# RAM_TheoreticalDiagram.net
KiCad netlist of a schematic drawn in EAGLE
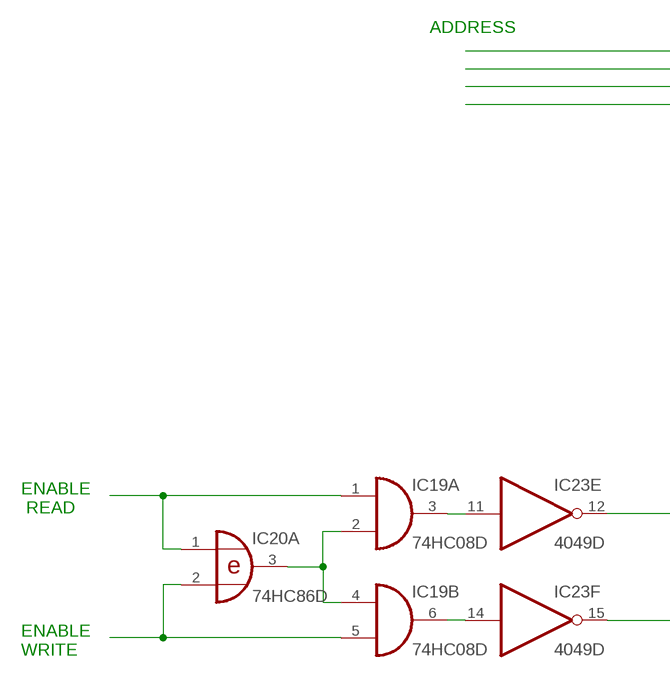
[diagram p0: schematic, sheet 1, part 1 of 2]
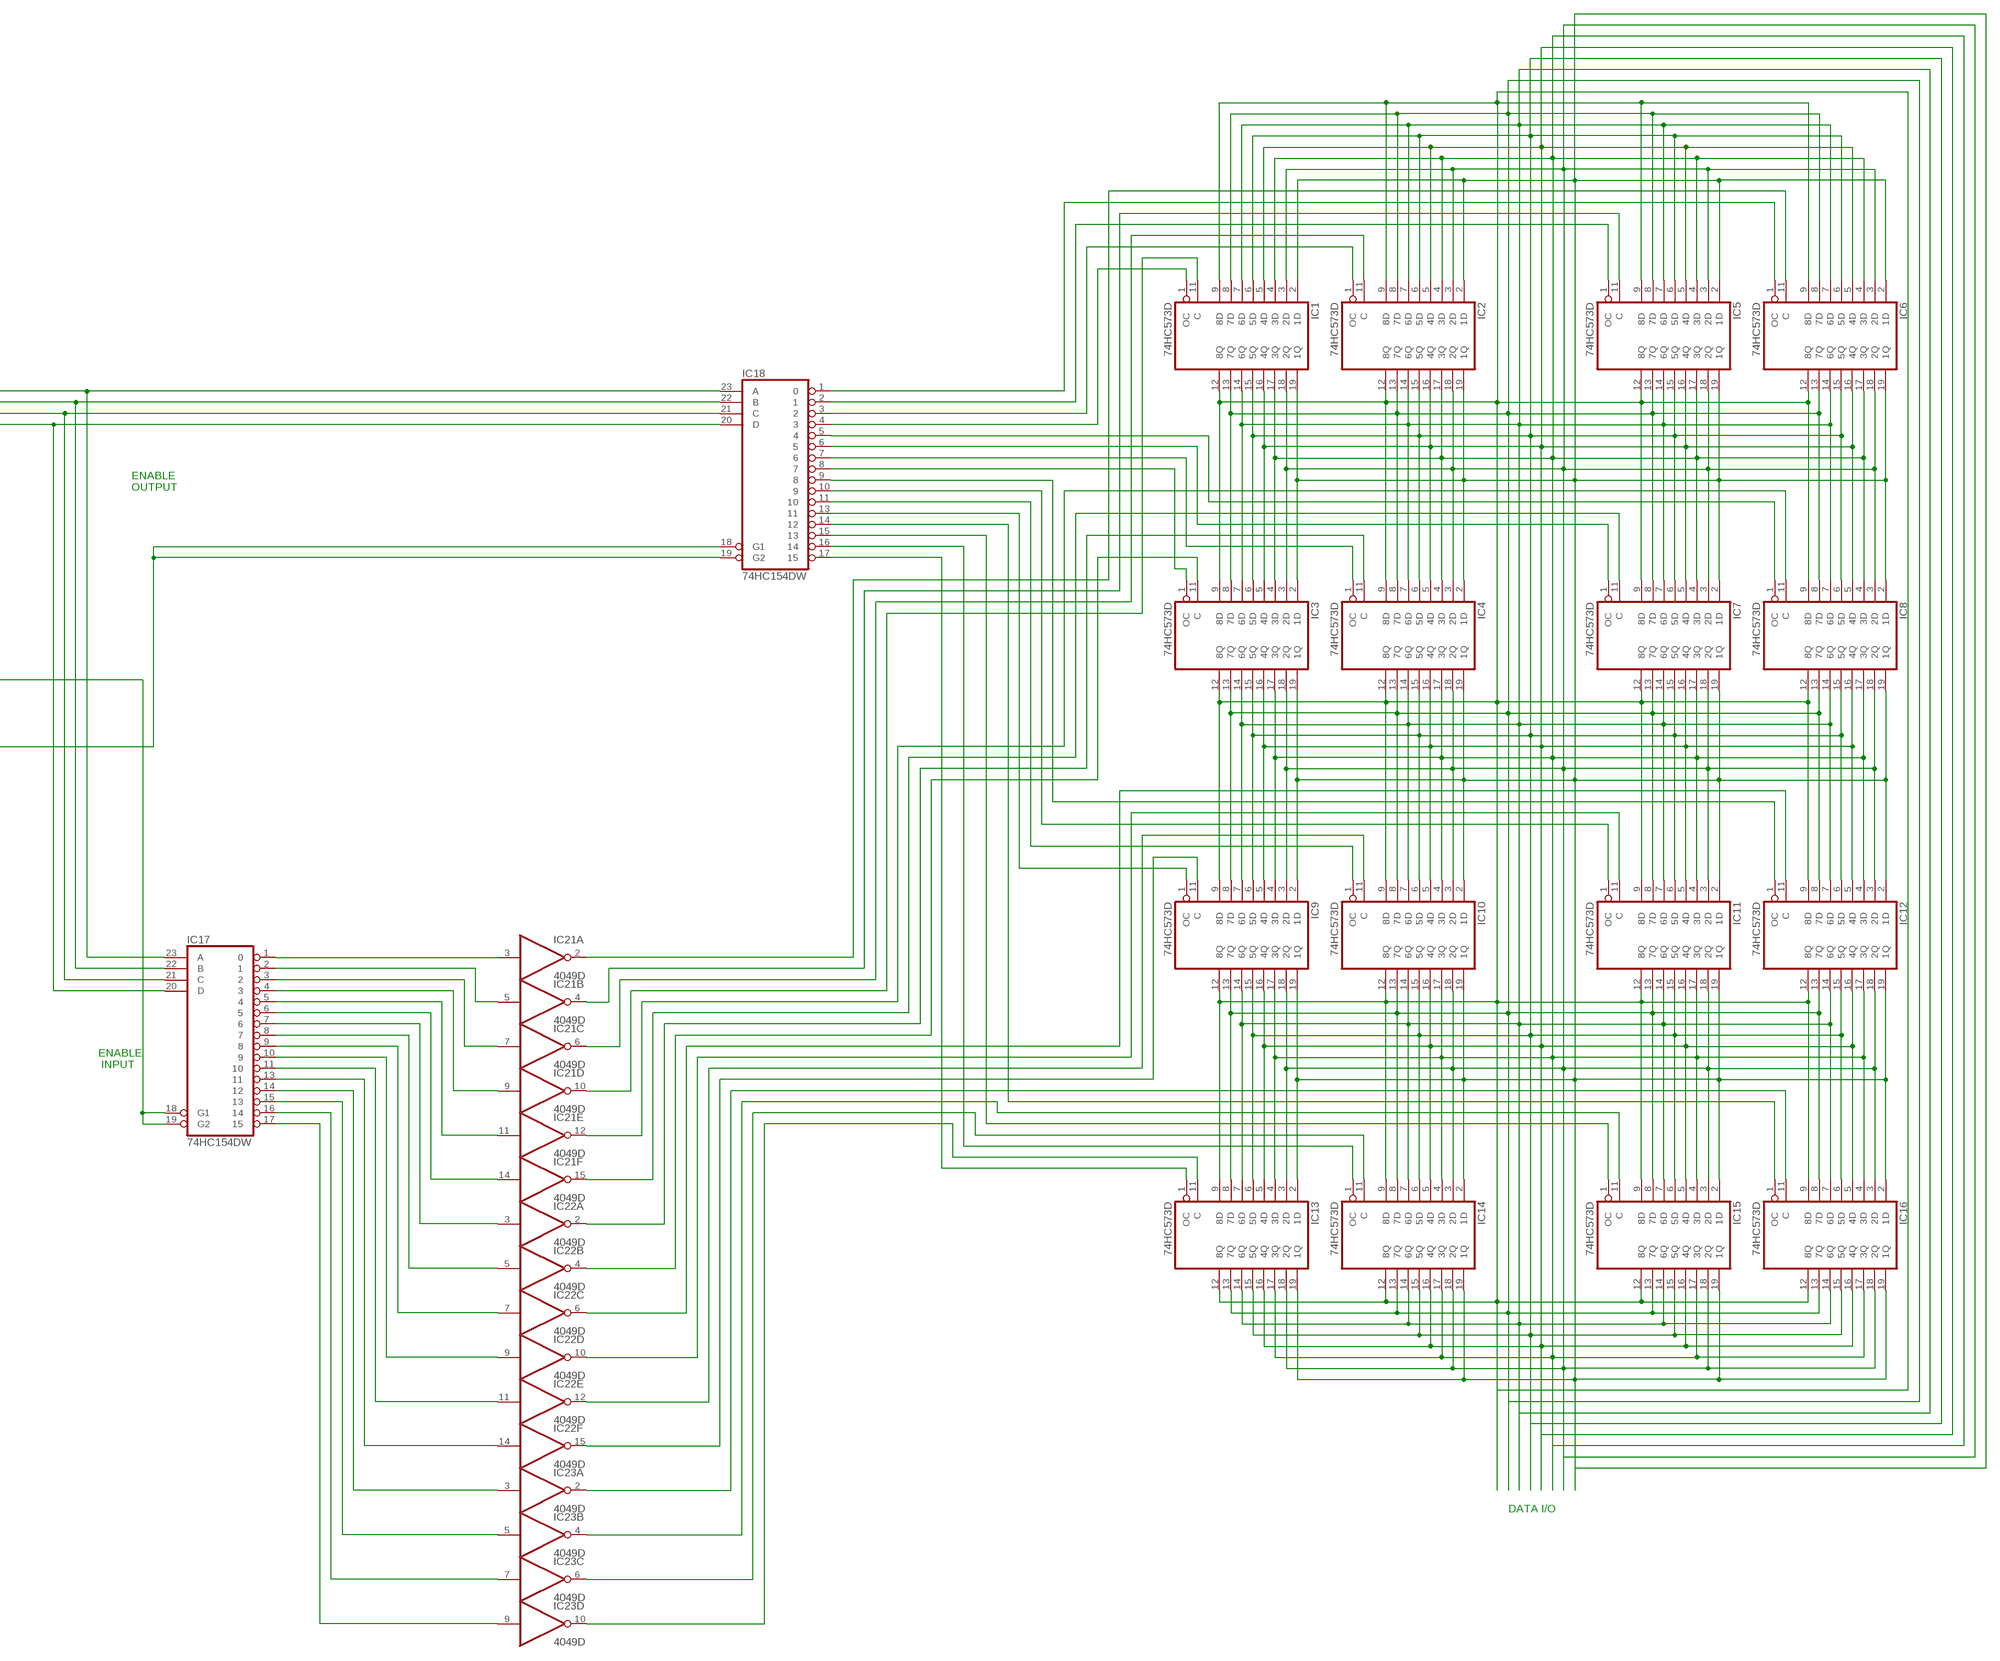
[diagram p1: schematic, sheet 1, part 2 of 2]

(export (version "E")
  (design (tool "Eeschema 10.0.6"))
  (components
    (comp (ref "IC1")
      (value "74HC573D")
      (footprint "eagle-import:SO20W")
      (libsource (lib "eagle-import") (part "74573DHC"))
    )
    (comp (ref "IC2")
      (value "74HC573D")
      (footprint "eagle-import:SO20W")
      (libsource (lib "eagle-import") (part "74573DHC"))
    )
    (comp (ref "IC3")
      (value "74HC573D")
      (footprint "eagle-import:SO20W")
      (libsource (lib "eagle-import") (part "74573DHC"))
    )
    (comp (ref "IC4")
      (value "74HC573D")
      (footprint "eagle-import:SO20W")
      (libsource (lib "eagle-import") (part "74573DHC"))
    )
    (comp (ref "IC5")
      (value "74HC573D")
      (footprint "eagle-import:SO20W")
      (libsource (lib "eagle-import") (part "74573DHC"))
    )
    (comp (ref "IC6")
      (value "74HC573D")
      (footprint "eagle-import:SO20W")
      (libsource (lib "eagle-import") (part "74573DHC"))
    )
    (comp (ref "IC7")
      (value "74HC573D")
      (footprint "eagle-import:SO20W")
      (libsource (lib "eagle-import") (part "74573DHC"))
    )
    (comp (ref "IC8")
      (value "74HC573D")
      (footprint "eagle-import:SO20W")
      (libsource (lib "eagle-import") (part "74573DHC"))
    )
    (comp (ref "IC9")
      (value "74HC573D")
      (footprint "eagle-import:SO20W")
      (libsource (lib "eagle-import") (part "74573DHC"))
    )
    (comp (ref "IC10")
      (value "74HC573D")
      (footprint "eagle-import:SO20W")
      (libsource (lib "eagle-import") (part "74573DHC"))
    )
    (comp (ref "IC11")
      (value "74HC573D")
      (footprint "eagle-import:SO20W")
      (libsource (lib "eagle-import") (part "74573DHC"))
    )
    (comp (ref "IC12")
      (value "74HC573D")
      (footprint "eagle-import:SO20W")
      (libsource (lib "eagle-import") (part "74573DHC"))
    )
    (comp (ref "IC13")
      (value "74HC573D")
      (footprint "eagle-import:SO20W")
      (libsource (lib "eagle-import") (part "74573DHC"))
    )
    (comp (ref "IC14")
      (value "74HC573D")
      (footprint "eagle-import:SO20W")
      (libsource (lib "eagle-import") (part "74573DHC"))
    )
    (comp (ref "IC15")
      (value "74HC573D")
      (footprint "eagle-import:SO20W")
      (libsource (lib "eagle-import") (part "74573DHC"))
    )
    (comp (ref "IC16")
      (value "74HC573D")
      (footprint "eagle-import:SO20W")
      (libsource (lib "eagle-import") (part "74573DHC"))
    )
    (comp (ref "IC17")
      (value "74HC154DW")
      (footprint "eagle-import:SO24W")
      (libsource (lib "eagle-import") (part "74154DWHC"))
    )
    (comp (ref "IC18")
      (value "74HC154DW")
      (footprint "eagle-import:SO24W")
      (libsource (lib "eagle-import") (part "74154DWHC"))
    )
    (comp (ref "IC19")
      (value "74HC08D")
      (footprint "eagle-import:SO14")
      (libsource (lib "eagle-import") (part "7408DHC"))
    )
    (comp (ref "IC20")
      (value "74HC86D")
      (footprint "eagle-import:SO14")
      (libsource (lib "eagle-import") (part "7486DHC"))
    )
    (comp (ref "IC21")
      (value "4049D")
      (footprint "eagle-import:SO16")
      (libsource (lib "eagle-import") (part "4049D"))
    )
    (comp (ref "IC22")
      (value "4049D")
      (footprint "eagle-import:SO16")
      (libsource (lib "eagle-import") (part "4049D"))
    )
    (comp (ref "IC23")
      (value "4049D")
      (footprint "eagle-import:SO16")
      (libsource (lib "eagle-import") (part "4049D"))
    )
  )
  (nets
    (net (code "1") (name "Net-(IC1A-C)") (class "Default")
      (node (ref "IC1") (pin "11") (pinfunction "C_11") (pintype "input"))
      (node (ref "IC21") (pin "10") (pinfunction "O_10") (pintype "output"))
    )
    (net (code "2") (name "Net-(IC10A-1D)") (class "Default")
      (node (ref "IC1") (pin "19") (pinfunction "1Q_19") (pintype "tri_state"))
      (node (ref "IC1") (pin "2") (pinfunction "1D_2") (pintype "input"))
      (node (ref "IC10") (pin "19") (pinfunction "1Q_19") (pintype "tri_state"))
      (node (ref "IC10") (pin "2") (pinfunction "1D_2") (pintype "input"))
      (node (ref "IC11") (pin "19") (pinfunction "1Q_19") (pintype "tri_state"))
      (node (ref "IC11") (pin "2") (pinfunction "1D_2") (pintype "input"))
      (node (ref "IC12") (pin "19") (pinfunction "1Q_19") (pintype "tri_state"))
      (node (ref "IC12") (pin "2") (pinfunction "1D_2") (pintype "input"))
      (node (ref "IC13") (pin "19") (pinfunction "1Q_19") (pintype "tri_state"))
      (node (ref "IC13") (pin "2") (pinfunction "1D_2") (pintype "input"))
      (node (ref "IC14") (pin "19") (pinfunction "1Q_19") (pintype "tri_state"))
      (node (ref "IC14") (pin "2") (pinfunction "1D_2") (pintype "input"))
      (node (ref "IC15") (pin "19") (pinfunction "1Q_19") (pintype "tri_state"))
      (node (ref "IC15") (pin "2") (pinfunction "1D_2") (pintype "input"))
      (node (ref "IC16") (pin "19") (pinfunction "1Q_19") (pintype "tri_state"))
      (node (ref "IC16") (pin "2") (pinfunction "1D_2") (pintype "input"))
      (node (ref "IC2") (pin "19") (pinfunction "1Q_19") (pintype "tri_state"))
      (node (ref "IC2") (pin "2") (pinfunction "1D_2") (pintype "input"))
      (node (ref "IC3") (pin "19") (pinfunction "1Q_19") (pintype "tri_state"))
      (node (ref "IC3") (pin "2") (pinfunction "1D_2") (pintype "input"))
      (node (ref "IC4") (pin "19") (pinfunction "1Q_19") (pintype "tri_state"))
      (node (ref "IC4") (pin "2") (pinfunction "1D_2") (pintype "input"))
      (node (ref "IC5") (pin "19") (pinfunction "1Q_19") (pintype "tri_state"))
      (node (ref "IC5") (pin "2") (pinfunction "1D_2") (pintype "input"))
      (node (ref "IC6") (pin "19") (pinfunction "1Q_19") (pintype "tri_state"))
      (node (ref "IC6") (pin "2") (pinfunction "1D_2") (pintype "input"))
      (node (ref "IC7") (pin "19") (pinfunction "1Q_19") (pintype "tri_state"))
      (node (ref "IC7") (pin "2") (pinfunction "1D_2") (pintype "input"))
      (node (ref "IC8") (pin "19") (pinfunction "1Q_19") (pintype "tri_state"))
      (node (ref "IC8") (pin "2") (pinfunction "1D_2") (pintype "input"))
      (node (ref "IC9") (pin "19") (pinfunction "1Q_19") (pintype "tri_state"))
      (node (ref "IC9") (pin "2") (pinfunction "1D_2") (pintype "input"))
    )
    (net (code "3") (name "Net-(IC10A-2D)") (class "Default")
      (node (ref "IC1") (pin "18") (pinfunction "2Q_18") (pintype "tri_state"))
      (node (ref "IC1") (pin "3") (pinfunction "2D_3") (pintype "input"))
      (node (ref "IC10") (pin "18") (pinfunction "2Q_18") (pintype "tri_state"))
      (node (ref "IC10") (pin "3") (pinfunction "2D_3") (pintype "input"))
      (node (ref "IC11") (pin "18") (pinfunction "2Q_18") (pintype "tri_state"))
      (node (ref "IC11") (pin "3") (pinfunction "2D_3") (pintype "input"))
      (node (ref "IC12") (pin "18") (pinfunction "2Q_18") (pintype "tri_state"))
      (node (ref "IC12") (pin "3") (pinfunction "2D_3") (pintype "input"))
      (node (ref "IC13") (pin "18") (pinfunction "2Q_18") (pintype "tri_state"))
      (node (ref "IC13") (pin "3") (pinfunction "2D_3") (pintype "input"))
      (node (ref "IC14") (pin "18") (pinfunction "2Q_18") (pintype "tri_state"))
      (node (ref "IC14") (pin "3") (pinfunction "2D_3") (pintype "input"))
      (node (ref "IC15") (pin "18") (pinfunction "2Q_18") (pintype "tri_state"))
      (node (ref "IC15") (pin "3") (pinfunction "2D_3") (pintype "input"))
      (node (ref "IC16") (pin "18") (pinfunction "2Q_18") (pintype "tri_state"))
      (node (ref "IC16") (pin "3") (pinfunction "2D_3") (pintype "input"))
      (node (ref "IC2") (pin "18") (pinfunction "2Q_18") (pintype "tri_state"))
      (node (ref "IC2") (pin "3") (pinfunction "2D_3") (pintype "input"))
      (node (ref "IC3") (pin "18") (pinfunction "2Q_18") (pintype "tri_state"))
      (node (ref "IC3") (pin "3") (pinfunction "2D_3") (pintype "input"))
      (node (ref "IC4") (pin "18") (pinfunction "2Q_18") (pintype "tri_state"))
      (node (ref "IC4") (pin "3") (pinfunction "2D_3") (pintype "input"))
      (node (ref "IC5") (pin "18") (pinfunction "2Q_18") (pintype "tri_state"))
      (node (ref "IC5") (pin "3") (pinfunction "2D_3") (pintype "input"))
      (node (ref "IC6") (pin "18") (pinfunction "2Q_18") (pintype "tri_state"))
      (node (ref "IC6") (pin "3") (pinfunction "2D_3") (pintype "input"))
      (node (ref "IC7") (pin "18") (pinfunction "2Q_18") (pintype "tri_state"))
      (node (ref "IC7") (pin "3") (pinfunction "2D_3") (pintype "input"))
      (node (ref "IC8") (pin "18") (pinfunction "2Q_18") (pintype "tri_state"))
      (node (ref "IC8") (pin "3") (pinfunction "2D_3") (pintype "input"))
      (node (ref "IC9") (pin "18") (pinfunction "2Q_18") (pintype "tri_state"))
      (node (ref "IC9") (pin "3") (pinfunction "2D_3") (pintype "input"))
    )
    (net (code "4") (name "Net-(IC10A-3D)") (class "Default")
      (node (ref "IC1") (pin "17") (pinfunction "3Q_17") (pintype "tri_state"))
      (node (ref "IC1") (pin "4") (pinfunction "3D_4") (pintype "input"))
      (node (ref "IC10") (pin "17") (pinfunction "3Q_17") (pintype "tri_state"))
      (node (ref "IC10") (pin "4") (pinfunction "3D_4") (pintype "input"))
      (node (ref "IC11") (pin "17") (pinfunction "3Q_17") (pintype "tri_state"))
      (node (ref "IC11") (pin "4") (pinfunction "3D_4") (pintype "input"))
      (node (ref "IC12") (pin "17") (pinfunction "3Q_17") (pintype "tri_state"))
      (node (ref "IC12") (pin "4") (pinfunction "3D_4") (pintype "input"))
      (node (ref "IC13") (pin "17") (pinfunction "3Q_17") (pintype "tri_state"))
      (node (ref "IC13") (pin "4") (pinfunction "3D_4") (pintype "input"))
      (node (ref "IC14") (pin "17") (pinfunction "3Q_17") (pintype "tri_state"))
      (node (ref "IC14") (pin "4") (pinfunction "3D_4") (pintype "input"))
      (node (ref "IC15") (pin "17") (pinfunction "3Q_17") (pintype "tri_state"))
      (node (ref "IC15") (pin "4") (pinfunction "3D_4") (pintype "input"))
      (node (ref "IC16") (pin "17") (pinfunction "3Q_17") (pintype "tri_state"))
      (node (ref "IC16") (pin "4") (pinfunction "3D_4") (pintype "input"))
      (node (ref "IC2") (pin "17") (pinfunction "3Q_17") (pintype "tri_state"))
      (node (ref "IC2") (pin "4") (pinfunction "3D_4") (pintype "input"))
      (node (ref "IC3") (pin "17") (pinfunction "3Q_17") (pintype "tri_state"))
      (node (ref "IC3") (pin "4") (pinfunction "3D_4") (pintype "input"))
      (node (ref "IC4") (pin "17") (pinfunction "3Q_17") (pintype "tri_state"))
      (node (ref "IC4") (pin "4") (pinfunction "3D_4") (pintype "input"))
      (node (ref "IC5") (pin "17") (pinfunction "3Q_17") (pintype "tri_state"))
      (node (ref "IC5") (pin "4") (pinfunction "3D_4") (pintype "input"))
      (node (ref "IC6") (pin "17") (pinfunction "3Q_17") (pintype "tri_state"))
      (node (ref "IC6") (pin "4") (pinfunction "3D_4") (pintype "input"))
      (node (ref "IC7") (pin "17") (pinfunction "3Q_17") (pintype "tri_state"))
      (node (ref "IC7") (pin "4") (pinfunction "3D_4") (pintype "input"))
      (node (ref "IC8") (pin "17") (pinfunction "3Q_17") (pintype "tri_state"))
      (node (ref "IC8") (pin "4") (pinfunction "3D_4") (pintype "input"))
      (node (ref "IC9") (pin "17") (pinfunction "3Q_17") (pintype "tri_state"))
      (node (ref "IC9") (pin "4") (pinfunction "3D_4") (pintype "input"))
    )
    (net (code "5") (name "Net-(IC10A-4D)") (class "Default")
      (node (ref "IC1") (pin "16") (pinfunction "4Q_16") (pintype "tri_state"))
      (node (ref "IC1") (pin "5") (pinfunction "4D_5") (pintype "input"))
      (node (ref "IC10") (pin "16") (pinfunction "4Q_16") (pintype "tri_state"))
      (node (ref "IC10") (pin "5") (pinfunction "4D_5") (pintype "input"))
      (node (ref "IC11") (pin "16") (pinfunction "4Q_16") (pintype "tri_state"))
      (node (ref "IC11") (pin "5") (pinfunction "4D_5") (pintype "input"))
      (node (ref "IC12") (pin "16") (pinfunction "4Q_16") (pintype "tri_state"))
      (node (ref "IC12") (pin "5") (pinfunction "4D_5") (pintype "input"))
      (node (ref "IC13") (pin "16") (pinfunction "4Q_16") (pintype "tri_state"))
      (node (ref "IC13") (pin "5") (pinfunction "4D_5") (pintype "input"))
      (node (ref "IC14") (pin "16") (pinfunction "4Q_16") (pintype "tri_state"))
      (node (ref "IC14") (pin "5") (pinfunction "4D_5") (pintype "input"))
      (node (ref "IC15") (pin "16") (pinfunction "4Q_16") (pintype "tri_state"))
      (node (ref "IC15") (pin "5") (pinfunction "4D_5") (pintype "input"))
      (node (ref "IC16") (pin "16") (pinfunction "4Q_16") (pintype "tri_state"))
      (node (ref "IC16") (pin "5") (pinfunction "4D_5") (pintype "input"))
      (node (ref "IC2") (pin "16") (pinfunction "4Q_16") (pintype "tri_state"))
      (node (ref "IC2") (pin "5") (pinfunction "4D_5") (pintype "input"))
      (node (ref "IC3") (pin "16") (pinfunction "4Q_16") (pintype "tri_state"))
      (node (ref "IC3") (pin "5") (pinfunction "4D_5") (pintype "input"))
      (node (ref "IC4") (pin "16") (pinfunction "4Q_16") (pintype "tri_state"))
      (node (ref "IC4") (pin "5") (pinfunction "4D_5") (pintype "input"))
      (node (ref "IC5") (pin "16") (pinfunction "4Q_16") (pintype "tri_state"))
      (node (ref "IC5") (pin "5") (pinfunction "4D_5") (pintype "input"))
      (node (ref "IC6") (pin "16") (pinfunction "4Q_16") (pintype "tri_state"))
      (node (ref "IC6") (pin "5") (pinfunction "4D_5") (pintype "input"))
      (node (ref "IC7") (pin "16") (pinfunction "4Q_16") (pintype "tri_state"))
      (node (ref "IC7") (pin "5") (pinfunction "4D_5") (pintype "input"))
      (node (ref "IC8") (pin "16") (pinfunction "4Q_16") (pintype "tri_state"))
      (node (ref "IC8") (pin "5") (pinfunction "4D_5") (pintype "input"))
      (node (ref "IC9") (pin "16") (pinfunction "4Q_16") (pintype "tri_state"))
      (node (ref "IC9") (pin "5") (pinfunction "4D_5") (pintype "input"))
    )
    (net (code "6") (name "Net-(IC10A-5D)") (class "Default")
      (node (ref "IC1") (pin "15") (pinfunction "5Q_15") (pintype "tri_state"))
      (node (ref "IC1") (pin "6") (pinfunction "5D_6") (pintype "input"))
      (node (ref "IC10") (pin "15") (pinfunction "5Q_15") (pintype "tri_state"))
      (node (ref "IC10") (pin "6") (pinfunction "5D_6") (pintype "input"))
      (node (ref "IC11") (pin "15") (pinfunction "5Q_15") (pintype "tri_state"))
      (node (ref "IC11") (pin "6") (pinfunction "5D_6") (pintype "input"))
      (node (ref "IC12") (pin "15") (pinfunction "5Q_15") (pintype "tri_state"))
      (node (ref "IC12") (pin "6") (pinfunction "5D_6") (pintype "input"))
      (node (ref "IC13") (pin "15") (pinfunction "5Q_15") (pintype "tri_state"))
      (node (ref "IC13") (pin "6") (pinfunction "5D_6") (pintype "input"))
      (node (ref "IC14") (pin "15") (pinfunction "5Q_15") (pintype "tri_state"))
      (node (ref "IC14") (pin "6") (pinfunction "5D_6") (pintype "input"))
      (node (ref "IC15") (pin "15") (pinfunction "5Q_15") (pintype "tri_state"))
      (node (ref "IC15") (pin "6") (pinfunction "5D_6") (pintype "input"))
      (node (ref "IC16") (pin "15") (pinfunction "5Q_15") (pintype "tri_state"))
      (node (ref "IC16") (pin "6") (pinfunction "5D_6") (pintype "input"))
      (node (ref "IC2") (pin "15") (pinfunction "5Q_15") (pintype "tri_state"))
      (node (ref "IC2") (pin "6") (pinfunction "5D_6") (pintype "input"))
      (node (ref "IC3") (pin "15") (pinfunction "5Q_15") (pintype "tri_state"))
      (node (ref "IC3") (pin "6") (pinfunction "5D_6") (pintype "input"))
      (node (ref "IC4") (pin "15") (pinfunction "5Q_15") (pintype "tri_state"))
      (node (ref "IC4") (pin "6") (pinfunction "5D_6") (pintype "input"))
      (node (ref "IC5") (pin "15") (pinfunction "5Q_15") (pintype "tri_state"))
      (node (ref "IC5") (pin "6") (pinfunction "5D_6") (pintype "input"))
      (node (ref "IC6") (pin "15") (pinfunction "5Q_15") (pintype "tri_state"))
      (node (ref "IC6") (pin "6") (pinfunction "5D_6") (pintype "input"))
      (node (ref "IC7") (pin "15") (pinfunction "5Q_15") (pintype "tri_state"))
      (node (ref "IC7") (pin "6") (pinfunction "5D_6") (pintype "input"))
      (node (ref "IC8") (pin "15") (pinfunction "5Q_15") (pintype "tri_state"))
      (node (ref "IC8") (pin "6") (pinfunction "5D_6") (pintype "input"))
      (node (ref "IC9") (pin "15") (pinfunction "5Q_15") (pintype "tri_state"))
      (node (ref "IC9") (pin "6") (pinfunction "5D_6") (pintype "input"))
    )
    (net (code "7") (name "Net-(IC10A-6D)") (class "Default")
      (node (ref "IC1") (pin "14") (pinfunction "6Q_14") (pintype "tri_state"))
      (node (ref "IC1") (pin "7") (pinfunction "6D_7") (pintype "input"))
      (node (ref "IC10") (pin "14") (pinfunction "6Q_14") (pintype "tri_state"))
      (node (ref "IC10") (pin "7") (pinfunction "6D_7") (pintype "input"))
      (node (ref "IC11") (pin "14") (pinfunction "6Q_14") (pintype "tri_state"))
      (node (ref "IC11") (pin "7") (pinfunction "6D_7") (pintype "input"))
      (node (ref "IC12") (pin "14") (pinfunction "6Q_14") (pintype "tri_state"))
      (node (ref "IC12") (pin "7") (pinfunction "6D_7") (pintype "input"))
      (node (ref "IC13") (pin "14") (pinfunction "6Q_14") (pintype "tri_state"))
      (node (ref "IC13") (pin "7") (pinfunction "6D_7") (pintype "input"))
      (node (ref "IC14") (pin "14") (pinfunction "6Q_14") (pintype "tri_state"))
      (node (ref "IC14") (pin "7") (pinfunction "6D_7") (pintype "input"))
      (node (ref "IC15") (pin "14") (pinfunction "6Q_14") (pintype "tri_state"))
      (node (ref "IC15") (pin "7") (pinfunction "6D_7") (pintype "input"))
      (node (ref "IC16") (pin "14") (pinfunction "6Q_14") (pintype "tri_state"))
      (node (ref "IC16") (pin "7") (pinfunction "6D_7") (pintype "input"))
      (node (ref "IC2") (pin "14") (pinfunction "6Q_14") (pintype "tri_state"))
      (node (ref "IC2") (pin "7") (pinfunction "6D_7") (pintype "input"))
      (node (ref "IC3") (pin "14") (pinfunction "6Q_14") (pintype "tri_state"))
      (node (ref "IC3") (pin "7") (pinfunction "6D_7") (pintype "input"))
      (node (ref "IC4") (pin "14") (pinfunction "6Q_14") (pintype "tri_state"))
      (node (ref "IC4") (pin "7") (pinfunction "6D_7") (pintype "input"))
      (node (ref "IC5") (pin "14") (pinfunction "6Q_14") (pintype "tri_state"))
      (node (ref "IC5") (pin "7") (pinfunction "6D_7") (pintype "input"))
      (node (ref "IC6") (pin "14") (pinfunction "6Q_14") (pintype "tri_state"))
      (node (ref "IC6") (pin "7") (pinfunction "6D_7") (pintype "input"))
      (node (ref "IC7") (pin "14") (pinfunction "6Q_14") (pintype "tri_state"))
      (node (ref "IC7") (pin "7") (pinfunction "6D_7") (pintype "input"))
      (node (ref "IC8") (pin "14") (pinfunction "6Q_14") (pintype "tri_state"))
      (node (ref "IC8") (pin "7") (pinfunction "6D_7") (pintype "input"))
      (node (ref "IC9") (pin "14") (pinfunction "6Q_14") (pintype "tri_state"))
      (node (ref "IC9") (pin "7") (pinfunction "6D_7") (pintype "input"))
    )
    (net (code "8") (name "Net-(IC10A-7D)") (class "Default")
      (node (ref "IC1") (pin "13") (pinfunction "7Q_13") (pintype "tri_state"))
      (node (ref "IC1") (pin "8") (pinfunction "7D_8") (pintype "input"))
      (node (ref "IC10") (pin "13") (pinfunction "7Q_13") (pintype "tri_state"))
      (node (ref "IC10") (pin "8") (pinfunction "7D_8") (pintype "input"))
      (node (ref "IC11") (pin "13") (pinfunction "7Q_13") (pintype "tri_state"))
      (node (ref "IC11") (pin "8") (pinfunction "7D_8") (pintype "input"))
      (node (ref "IC12") (pin "13") (pinfunction "7Q_13") (pintype "tri_state"))
      (node (ref "IC12") (pin "8") (pinfunction "7D_8") (pintype "input"))
      (node (ref "IC13") (pin "13") (pinfunction "7Q_13") (pintype "tri_state"))
      (node (ref "IC13") (pin "8") (pinfunction "7D_8") (pintype "input"))
      (node (ref "IC14") (pin "13") (pinfunction "7Q_13") (pintype "tri_state"))
      (node (ref "IC14") (pin "8") (pinfunction "7D_8") (pintype "input"))
      (node (ref "IC15") (pin "13") (pinfunction "7Q_13") (pintype "tri_state"))
      (node (ref "IC15") (pin "8") (pinfunction "7D_8") (pintype "input"))
      (node (ref "IC16") (pin "13") (pinfunction "7Q_13") (pintype "tri_state"))
      (node (ref "IC16") (pin "8") (pinfunction "7D_8") (pintype "input"))
      (node (ref "IC2") (pin "13") (pinfunction "7Q_13") (pintype "tri_state"))
      (node (ref "IC2") (pin "8") (pinfunction "7D_8") (pintype "input"))
      (node (ref "IC3") (pin "13") (pinfunction "7Q_13") (pintype "tri_state"))
      (node (ref "IC3") (pin "8") (pinfunction "7D_8") (pintype "input"))
      (node (ref "IC4") (pin "13") (pinfunction "7Q_13") (pintype "tri_state"))
      (node (ref "IC4") (pin "8") (pinfunction "7D_8") (pintype "input"))
      (node (ref "IC5") (pin "13") (pinfunction "7Q_13") (pintype "tri_state"))
      (node (ref "IC5") (pin "8") (pinfunction "7D_8") (pintype "input"))
      (node (ref "IC6") (pin "13") (pinfunction "7Q_13") (pintype "tri_state"))
      (node (ref "IC6") (pin "8") (pinfunction "7D_8") (pintype "input"))
      (node (ref "IC7") (pin "13") (pinfunction "7Q_13") (pintype "tri_state"))
      (node (ref "IC7") (pin "8") (pinfunction "7D_8") (pintype "input"))
      (node (ref "IC8") (pin "13") (pinfunction "7Q_13") (pintype "tri_state"))
      (node (ref "IC8") (pin "8") (pinfunction "7D_8") (pintype "input"))
      (node (ref "IC9") (pin "13") (pinfunction "7Q_13") (pintype "tri_state"))
      (node (ref "IC9") (pin "8") (pinfunction "7D_8") (pintype "input"))
    )
    (net (code "9") (name "Net-(IC10A-8D)") (class "Default")
      (node (ref "IC1") (pin "12") (pinfunction "8Q_12") (pintype "tri_state"))
      (node (ref "IC1") (pin "9") (pinfunction "8D_9") (pintype "input"))
      (node (ref "IC10") (pin "12") (pinfunction "8Q_12") (pintype "tri_state"))
      (node (ref "IC10") (pin "9") (pinfunction "8D_9") (pintype "input"))
      (node (ref "IC11") (pin "12") (pinfunction "8Q_12") (pintype "tri_state"))
      (node (ref "IC11") (pin "9") (pinfunction "8D_9") (pintype "input"))
      (node (ref "IC12") (pin "12") (pinfunction "8Q_12") (pintype "tri_state"))
      (node (ref "IC12") (pin "9") (pinfunction "8D_9") (pintype "input"))
      (node (ref "IC13") (pin "12") (pinfunction "8Q_12") (pintype "tri_state"))
      (node (ref "IC13") (pin "9") (pinfunction "8D_9") (pintype "input"))
      (node (ref "IC14") (pin "12") (pinfunction "8Q_12") (pintype "tri_state"))
      (node (ref "IC14") (pin "9") (pinfunction "8D_9") (pintype "input"))
      (node (ref "IC15") (pin "12") (pinfunction "8Q_12") (pintype "tri_state"))
      (node (ref "IC15") (pin "9") (pinfunction "8D_9") (pintype "input"))
      (node (ref "IC16") (pin "12") (pinfunction "8Q_12") (pintype "tri_state"))
      (node (ref "IC16") (pin "9") (pinfunction "8D_9") (pintype "input"))
      (node (ref "IC2") (pin "12") (pinfunction "8Q_12") (pintype "tri_state"))
      (node (ref "IC2") (pin "9") (pinfunction "8D_9") (pintype "input"))
      (node (ref "IC3") (pin "12") (pinfunction "8Q_12") (pintype "tri_state"))
      (node (ref "IC3") (pin "9") (pinfunction "8D_9") (pintype "input"))
      (node (ref "IC4") (pin "12") (pinfunction "8Q_12") (pintype "tri_state"))
      (node (ref "IC4") (pin "9") (pinfunction "8D_9") (pintype "input"))
      (node (ref "IC5") (pin "12") (pinfunction "8Q_12") (pintype "tri_state"))
      (node (ref "IC5") (pin "9") (pinfunction "8D_9") (pintype "input"))
      (node (ref "IC6") (pin "12") (pinfunction "8Q_12") (pintype "tri_state"))
      (node (ref "IC6") (pin "9") (pinfunction "8D_9") (pintype "input"))
      (node (ref "IC7") (pin "12") (pinfunction "8Q_12") (pintype "tri_state"))
      (node (ref "IC7") (pin "9") (pinfunction "8D_9") (pintype "input"))
      (node (ref "IC8") (pin "12") (pinfunction "8Q_12") (pintype "tri_state"))
      (node (ref "IC8") (pin "9") (pinfunction "8D_9") (pintype "input"))
      (node (ref "IC9") (pin "12") (pinfunction "8Q_12") (pintype "tri_state"))
      (node (ref "IC9") (pin "9") (pinfunction "8D_9") (pintype "input"))
    )
    (net (code "10") (name "Net-(IC10A-C)") (class "Default")
      (node (ref "IC10") (pin "11") (pinfunction "C_11") (pintype "input"))
      (node (ref "IC22") (pin "12") (pinfunction "O_12") (pintype "output"))
    )
    (net (code "11") (name "Net-(IC10A-OC)") (class "Default")
      (node (ref "IC10") (pin "1") (pinfunction "OC_1") (pintype "input"))
      (node (ref "IC18") (pin "11") (pinfunction "10_11") (pintype "output"))
    )
    (net (code "12") (name "Net-(IC11A-C)") (class "Default")
      (node (ref "IC11") (pin "11") (pinfunction "C_11") (pintype "input"))
      (node (ref "IC22") (pin "10") (pinfunction "O_10") (pintype "output"))
    )
    (net (code "13") (name "Net-(IC11A-OC)") (class "Default")
      (node (ref "IC11") (pin "1") (pinfunction "OC_1") (pintype "input"))
      (node (ref "IC18") (pin "10") (pinfunction "9_10") (pintype "output"))
    )
    (net (code "14") (name "Net-(IC12A-C)") (class "Default")
      (node (ref "IC12") (pin "11") (pinfunction "C_11") (pintype "input"))
      (node (ref "IC22") (pin "6") (pinfunction "O_6") (pintype "output"))
    )
    (net (code "15") (name "Net-(IC12A-OC)") (class "Default")
      (node (ref "IC12") (pin "1") (pinfunction "OC_1") (pintype "input"))
      (node (ref "IC18") (pin "9") (pinfunction "8_9") (pintype "output"))
    )
    (net (code "16") (name "Net-(IC13A-C)") (class "Default")
      (node (ref "IC13") (pin "11") (pinfunction "C_11") (pintype "input"))
      (node (ref "IC23") (pin "10") (pinfunction "O_10") (pintype "output"))
    )
    (net (code "17") (name "Net-(IC13A-OC)") (class "Default")
      (node (ref "IC13") (pin "1") (pinfunction "OC_1") (pintype "input"))
      (node (ref "IC18") (pin "17") (pinfunction "15_17") (pintype "output"))
    )
    (net (code "18") (name "Net-(IC14A-C)") (class "Default")
      (node (ref "IC14") (pin "11") (pinfunction "C_11") (pintype "input"))
      (node (ref "IC23") (pin "6") (pinfunction "O_6") (pintype "output"))
    )
    (net (code "19") (name "Net-(IC14A-OC)") (class "Default")
      (node (ref "IC14") (pin "1") (pinfunction "OC_1") (pintype "input"))
      (node (ref "IC18") (pin "16") (pinfunction "14_16") (pintype "output"))
    )
    (net (code "20") (name "Net-(IC15A-C)") (class "Default")
      (node (ref "IC15") (pin "11") (pinfunction "C_11") (pintype "input"))
      (node (ref "IC23") (pin "4") (pinfunction "O_4") (pintype "output"))
    )
    (net (code "21") (name "Net-(IC15A-OC)") (class "Default")
      (node (ref "IC15") (pin "1") (pinfunction "OC_1") (pintype "input"))
      (node (ref "IC18") (pin "15") (pinfunction "13_15") (pintype "output"))
    )
    (net (code "22") (name "Net-(IC16A-C)") (class "Default")
      (node (ref "IC16") (pin "11") (pinfunction "C_11") (pintype "input"))
      (node (ref "IC23") (pin "2") (pinfunction "O_2") (pintype "output"))
    )
    (net (code "23") (name "Net-(IC16A-OC)") (class "Default")
      (node (ref "IC16") (pin "1") (pinfunction "OC_1") (pintype "input"))
      (node (ref "IC18") (pin "14") (pinfunction "12_14") (pintype "output"))
    )
    (net (code "24") (name "Net-(IC17A-0)") (class "Default")
      (node (ref "IC17") (pin "1") (pinfunction "0_1") (pintype "output"))
      (node (ref "IC21") (pin "3") (pinfunction "I_3") (pintype "input"))
    )
    (net (code "25") (name "Net-(IC17A-1)") (class "Default")
      (node (ref "IC17") (pin "2") (pinfunction "1_2") (pintype "output"))
      (node (ref "IC21") (pin "5") (pinfunction "I_5") (pintype "input"))
    )
    (net (code "26") (name "Net-(IC17A-2)") (class "Default")
      (node (ref "IC17") (pin "3") (pinfunction "2_3") (pintype "output"))
      (node (ref "IC21") (pin "7") (pinfunction "I_7") (pintype "input"))
    )
    (net (code "27") (name "Net-(IC17A-3)") (class "Default")
      (node (ref "IC17") (pin "4") (pinfunction "3_4") (pintype "output"))
      (node (ref "IC21") (pin "9") (pinfunction "I_9") (pintype "input"))
    )
    (net (code "28") (name "Net-(IC17A-4)") (class "Default")
      (node (ref "IC17") (pin "5") (pinfunction "4_5") (pintype "output"))
      (node (ref "IC21") (pin "11") (pinfunction "I_11") (pintype "input"))
    )
    (net (code "29") (name "Net-(IC17A-5)") (class "Default")
      (node (ref "IC17") (pin "6") (pinfunction "5_6") (pintype "output"))
      (node (ref "IC21") (pin "14") (pinfunction "I_14") (pintype "input"))
    )
    (net (code "30") (name "Net-(IC17A-6)") (class "Default")
      (node (ref "IC17") (pin "7") (pinfunction "6_7") (pintype "output"))
      (node (ref "IC22") (pin "3") (pinfunction "I_3") (pintype "input"))
    )
    (net (code "31") (name "Net-(IC17A-7)") (class "Default")
      (node (ref "IC17") (pin "8") (pinfunction "7_8") (pintype "output"))
      (node (ref "IC22") (pin "5") (pinfunction "I_5") (pintype "input"))
    )
    (net (code "32") (name "Net-(IC17A-8)") (class "Default")
      (node (ref "IC17") (pin "9") (pinfunction "8_9") (pintype "output"))
      (node (ref "IC22") (pin "7") (pinfunction "I_7") (pintype "input"))
    )
    (net (code "33") (name "Net-(IC17A-9)") (class "Default")
      (node (ref "IC17") (pin "10") (pinfunction "9_10") (pintype "output"))
      (node (ref "IC22") (pin "9") (pinfunction "I_9") (pintype "input"))
    )
    (net (code "34") (name "Net-(IC17A-10)") (class "Default")
      (node (ref "IC17") (pin "11") (pinfunction "10_11") (pintype "output"))
      (node (ref "IC22") (pin "11") (pinfunction "I_11") (pintype "input"))
    )
    (net (code "35") (name "Net-(IC17A-11)") (class "Default")
      (node (ref "IC17") (pin "13") (pinfunction "11_13") (pintype "output"))
      (node (ref "IC22") (pin "14") (pinfunction "I_14") (pintype "input"))
    )
    (net (code "36") (name "Net-(IC17A-12)") (class "Default")
      (node (ref "IC17") (pin "14") (pinfunction "12_14") (pintype "output"))
      (node (ref "IC23") (pin "3") (pinfunction "I_3") (pintype "input"))
    )
    (net (code "37") (name "Net-(IC17A-13)") (class "Default")
      (node (ref "IC17") (pin "15") (pinfunction "13_15") (pintype "output"))
      (node (ref "IC23") (pin "5") (pinfunction "I_5") (pintype "input"))
    )
    (net (code "38") (name "Net-(IC17A-14)") (class "Default")
      (node (ref "IC17") (pin "16") (pinfunction "14_16") (pintype "output"))
      (node (ref "IC23") (pin "7") (pinfunction "I_7") (pintype "input"))
    )
    (net (code "39") (name "Net-(IC17A-15)") (class "Default")
      (node (ref "IC17") (pin "17") (pinfunction "15_17") (pintype "output"))
      (node (ref "IC23") (pin "9") (pinfunction "I_9") (pintype "input"))
    )
    (net (code "40") (name "Net-(IC17A-A)") (class "Default")
      (node (ref "IC17") (pin "23") (pinfunction "A_23") (pintype "input"))
      (node (ref "IC18") (pin "23") (pinfunction "A_23") (pintype "input"))
    )
    (net (code "41") (name "Net-(IC17A-B)") (class "Default")
      (node (ref "IC17") (pin "22") (pinfunction "B_22") (pintype "input"))
      (node (ref "IC18") (pin "22") (pinfunction "B_22") (pintype "input"))
    )
    (net (code "42") (name "Net-(IC17A-C)") (class "Default")
      (node (ref "IC17") (pin "21") (pinfunction "C_21") (pintype "input"))
      (node (ref "IC18") (pin "21") (pinfunction "C_21") (pintype "input"))
    )
    (net (code "43") (name "Net-(IC17A-D)") (class "Default")
      (node (ref "IC17") (pin "20") (pinfunction "D_20") (pintype "input"))
      (node (ref "IC18") (pin "20") (pinfunction "D_20") (pintype "input"))
    )
    (net (code "44") (name "Net-(IC17A-G1)") (class "Default")
      (node (ref "IC17") (pin "18") (pinfunction "G1_18") (pintype "input"))
      (node (ref "IC17") (pin "19") (pinfunction "G2_19") (pintype "input"))
      (node (ref "IC23") (pin "12") (pinfunction "O_12") (pintype "output"))
    )
    (net (code "45") (name "Net-(IC18A-0)") (class "Default")
      (node (ref "IC18") (pin "1") (pinfunction "0_1") (pintype "output"))
      (node (ref "IC6") (pin "1") (pinfunction "OC_1") (pintype "input"))
    )
    (net (code "46") (name "Net-(IC18A-1)") (class "Default")
      (node (ref "IC18") (pin "2") (pinfunction "1_2") (pintype "output"))
      (node (ref "IC5") (pin "1") (pinfunction "OC_1") (pintype "input"))
    )
    (net (code "47") (name "Net-(IC18A-2)") (class "Default")
      (node (ref "IC18") (pin "3") (pinfunction "2_3") (pintype "output"))
      (node (ref "IC2") (pin "1") (pinfunction "OC_1") (pintype "input"))
    )
    (net (code "48") (name "Net-(IC18A-3)") (class "Default")
      (node (ref "IC1") (pin "1") (pinfunction "OC_1") (pintype "input"))
      (node (ref "IC18") (pin "4") (pinfunction "3_4") (pintype "output"))
    )
    (net (code "49") (name "Net-(IC18A-4)") (class "Default")
      (node (ref "IC18") (pin "5") (pinfunction "4_5") (pintype "output"))
      (node (ref "IC8") (pin "1") (pinfunction "OC_1") (pintype "input"))
    )
    (net (code "50") (name "Net-(IC18A-5)") (class "Default")
      (node (ref "IC18") (pin "6") (pinfunction "5_6") (pintype "output"))
      (node (ref "IC7") (pin "1") (pinfunction "OC_1") (pintype "input"))
    )
    (net (code "51") (name "Net-(IC18A-6)") (class "Default")
      (node (ref "IC18") (pin "7") (pinfunction "6_7") (pintype "output"))
      (node (ref "IC4") (pin "1") (pinfunction "OC_1") (pintype "input"))
    )
    (net (code "52") (name "Net-(IC18A-7)") (class "Default")
      (node (ref "IC18") (pin "8") (pinfunction "7_8") (pintype "output"))
      (node (ref "IC3") (pin "1") (pinfunction "OC_1") (pintype "input"))
    )
    (net (code "53") (name "Net-(IC18A-11)") (class "Default")
      (node (ref "IC18") (pin "13") (pinfunction "11_13") (pintype "output"))
      (node (ref "IC9") (pin "1") (pinfunction "OC_1") (pintype "input"))
    )
    (net (code "54") (name "Net-(IC18A-G1)") (class "Default")
      (node (ref "IC18") (pin "18") (pinfunction "G1_18") (pintype "input"))
      (node (ref "IC18") (pin "19") (pinfunction "G2_19") (pintype "input"))
      (node (ref "IC23") (pin "15") (pinfunction "O_15") (pintype "output"))
    )
    (net (code "55") (name "Net-(IC19A-I0)") (class "Default")
      (node (ref "IC19") (pin "1") (pinfunction "I0_1") (pintype "input"))
      (node (ref "IC20") (pin "1") (pinfunction "I0_1") (pintype "input"))
    )
    (net (code "56") (name "Net-(IC19A-I1)") (class "Default")
      (node (ref "IC19") (pin "2") (pinfunction "I1_2") (pintype "input"))
      (node (ref "IC19") (pin "4") (pinfunction "I0_4") (pintype "input"))
      (node (ref "IC20") (pin "3") (pinfunction "O_3") (pintype "output"))
    )
    (net (code "57") (name "Net-(IC19A-O)") (class "Default")
      (node (ref "IC19") (pin "3") (pinfunction "O_3") (pintype "output"))
      (node (ref "IC23") (pin "11") (pinfunction "I_11") (pintype "input"))
    )
    (net (code "58") (name "Net-(IC19B-I1)") (class "Default")
      (node (ref "IC19") (pin "5") (pinfunction "I1_5") (pintype "input"))
      (node (ref "IC20") (pin "2") (pinfunction "I1_2") (pintype "input"))
    )
    (net (code "59") (name "Net-(IC19B-O)") (class "Default")
      (node (ref "IC19") (pin "6") (pinfunction "O_6") (pintype "output"))
      (node (ref "IC23") (pin "14") (pinfunction "I_14") (pintype "input"))
    )
    (net (code "60") (name "Net-(IC21A-O)") (class "Default")
      (node (ref "IC21") (pin "2") (pinfunction "O_2") (pintype "output"))
      (node (ref "IC6") (pin "11") (pinfunction "C_11") (pintype "input"))
    )
    (net (code "61") (name "Net-(IC21B-O)") (class "Default")
      (node (ref "IC21") (pin "4") (pinfunction "O_4") (pintype "output"))
      (node (ref "IC5") (pin "11") (pinfunction "C_11") (pintype "input"))
    )
    (net (code "62") (name "Net-(IC21C-O)") (class "Default")
      (node (ref "IC2") (pin "11") (pinfunction "C_11") (pintype "input"))
      (node (ref "IC21") (pin "6") (pinfunction "O_6") (pintype "output"))
    )
    (net (code "63") (name "Net-(IC21E-O)") (class "Default")
      (node (ref "IC21") (pin "12") (pinfunction "O_12") (pintype "output"))
      (node (ref "IC8") (pin "11") (pinfunction "C_11") (pintype "input"))
    )
    (net (code "64") (name "Net-(IC21F-O)") (class "Default")
      (node (ref "IC21") (pin "15") (pinfunction "O_15") (pintype "output"))
      (node (ref "IC7") (pin "11") (pinfunction "C_11") (pintype "input"))
    )
    (net (code "65") (name "Net-(IC22A-O)") (class "Default")
      (node (ref "IC22") (pin "2") (pinfunction "O_2") (pintype "output"))
      (node (ref "IC4") (pin "11") (pinfunction "C_11") (pintype "input"))
    )
    (net (code "66") (name "Net-(IC22B-O)") (class "Default")
      (node (ref "IC22") (pin "4") (pinfunction "O_4") (pintype "output"))
      (node (ref "IC3") (pin "11") (pinfunction "C_11") (pintype "input"))
    )
    (net (code "67") (name "Net-(IC22F-O)") (class "Default")
      (node (ref "IC22") (pin "15") (pinfunction "O_15") (pintype "output"))
      (node (ref "IC9") (pin "11") (pinfunction "C_11") (pintype "input"))
    )
  )
)
